# FieldBUS_RTU.net
KiCad netlist of a schematic drawn in Altium Designer
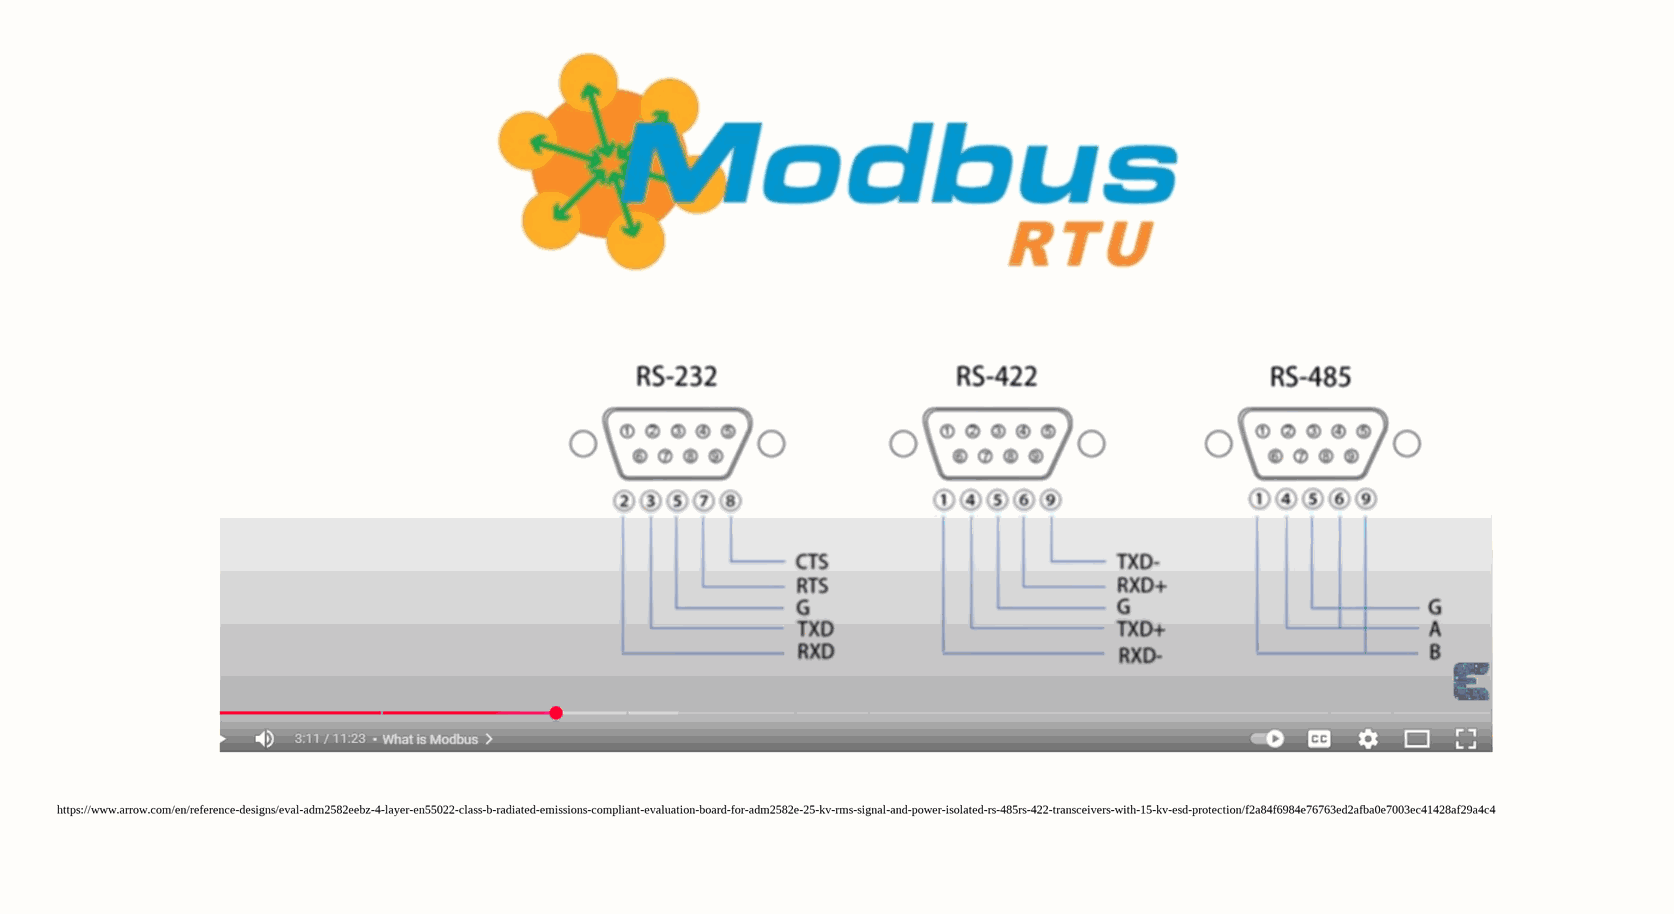
[diagram p0: FieldBUS_RTU.SchDoc, top left]
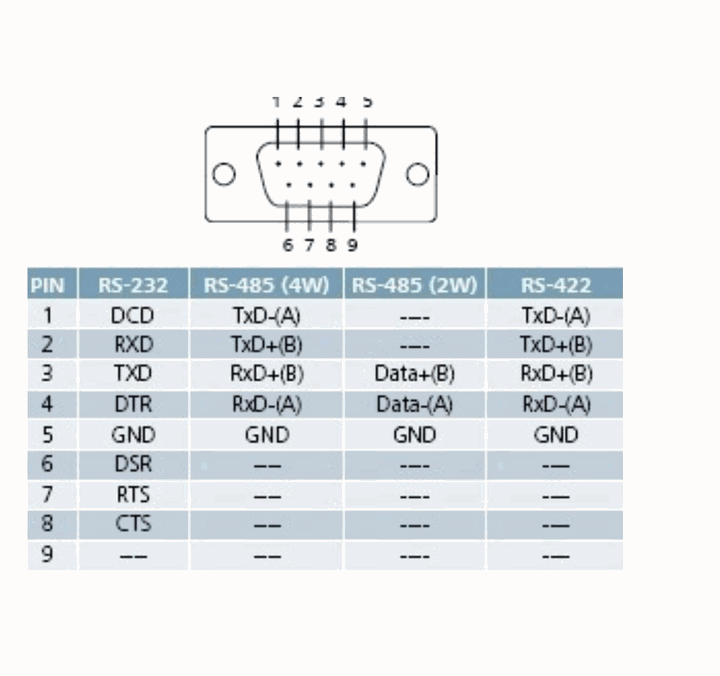
[diagram p1: FieldBUS_RTU.SchDoc, top right]
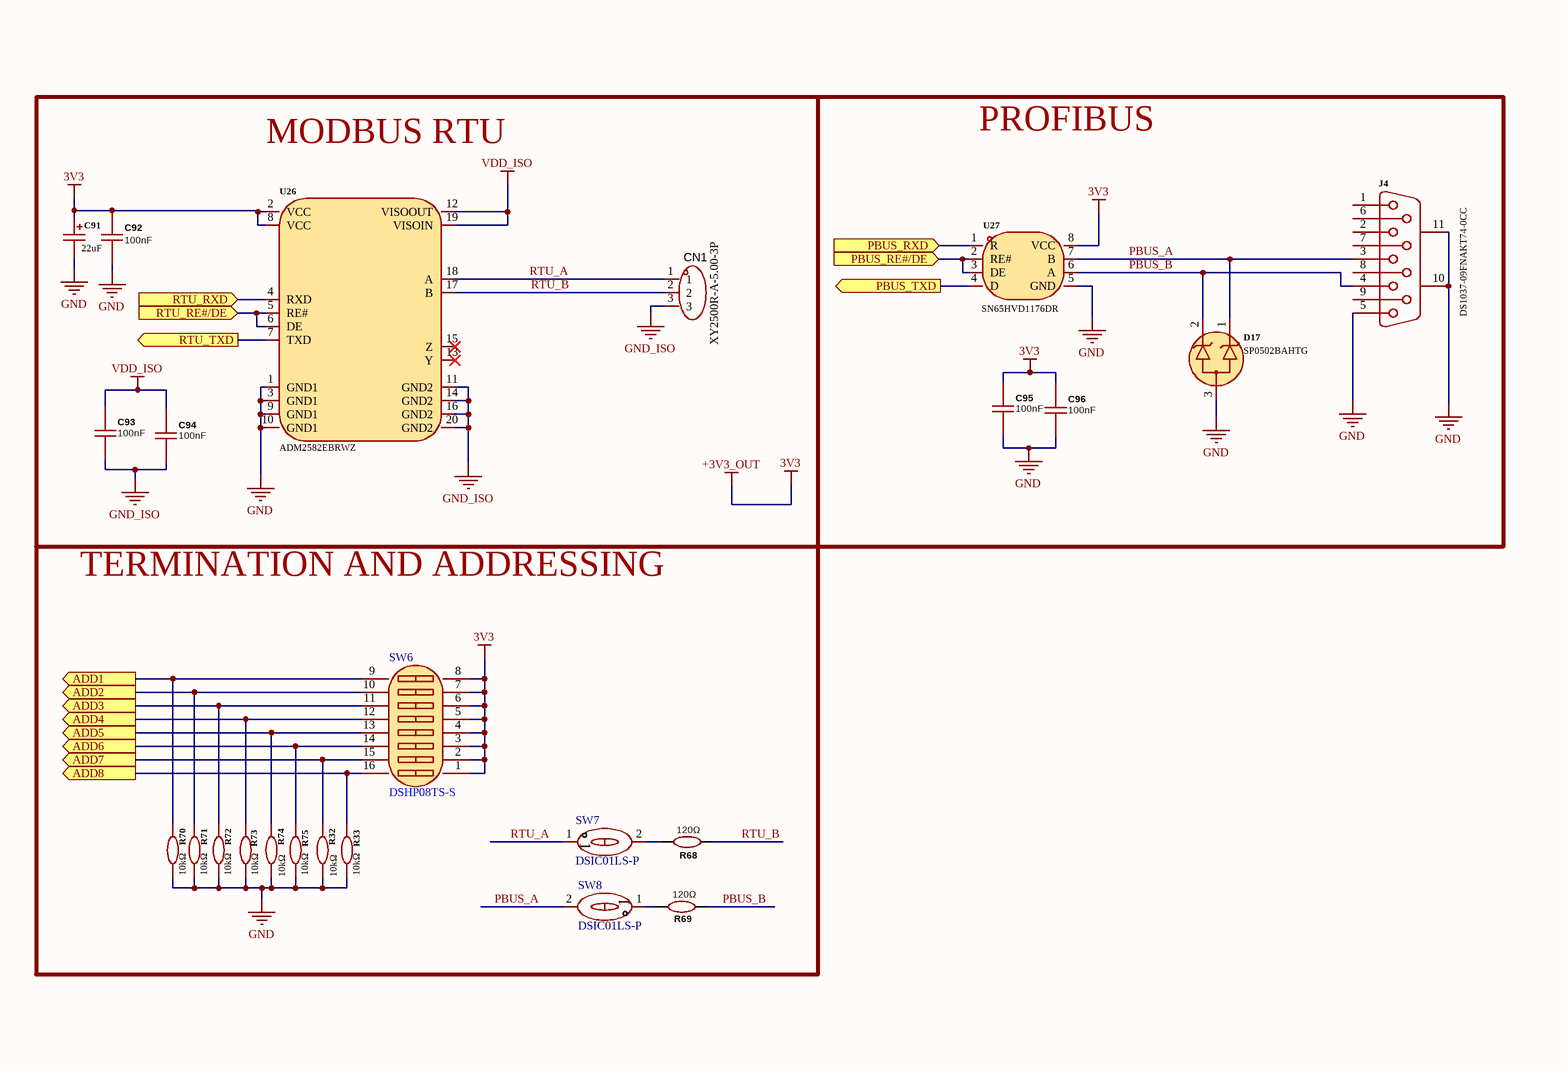
[diagram p2: FieldBUS_RTU.SchDoc, bottom left]
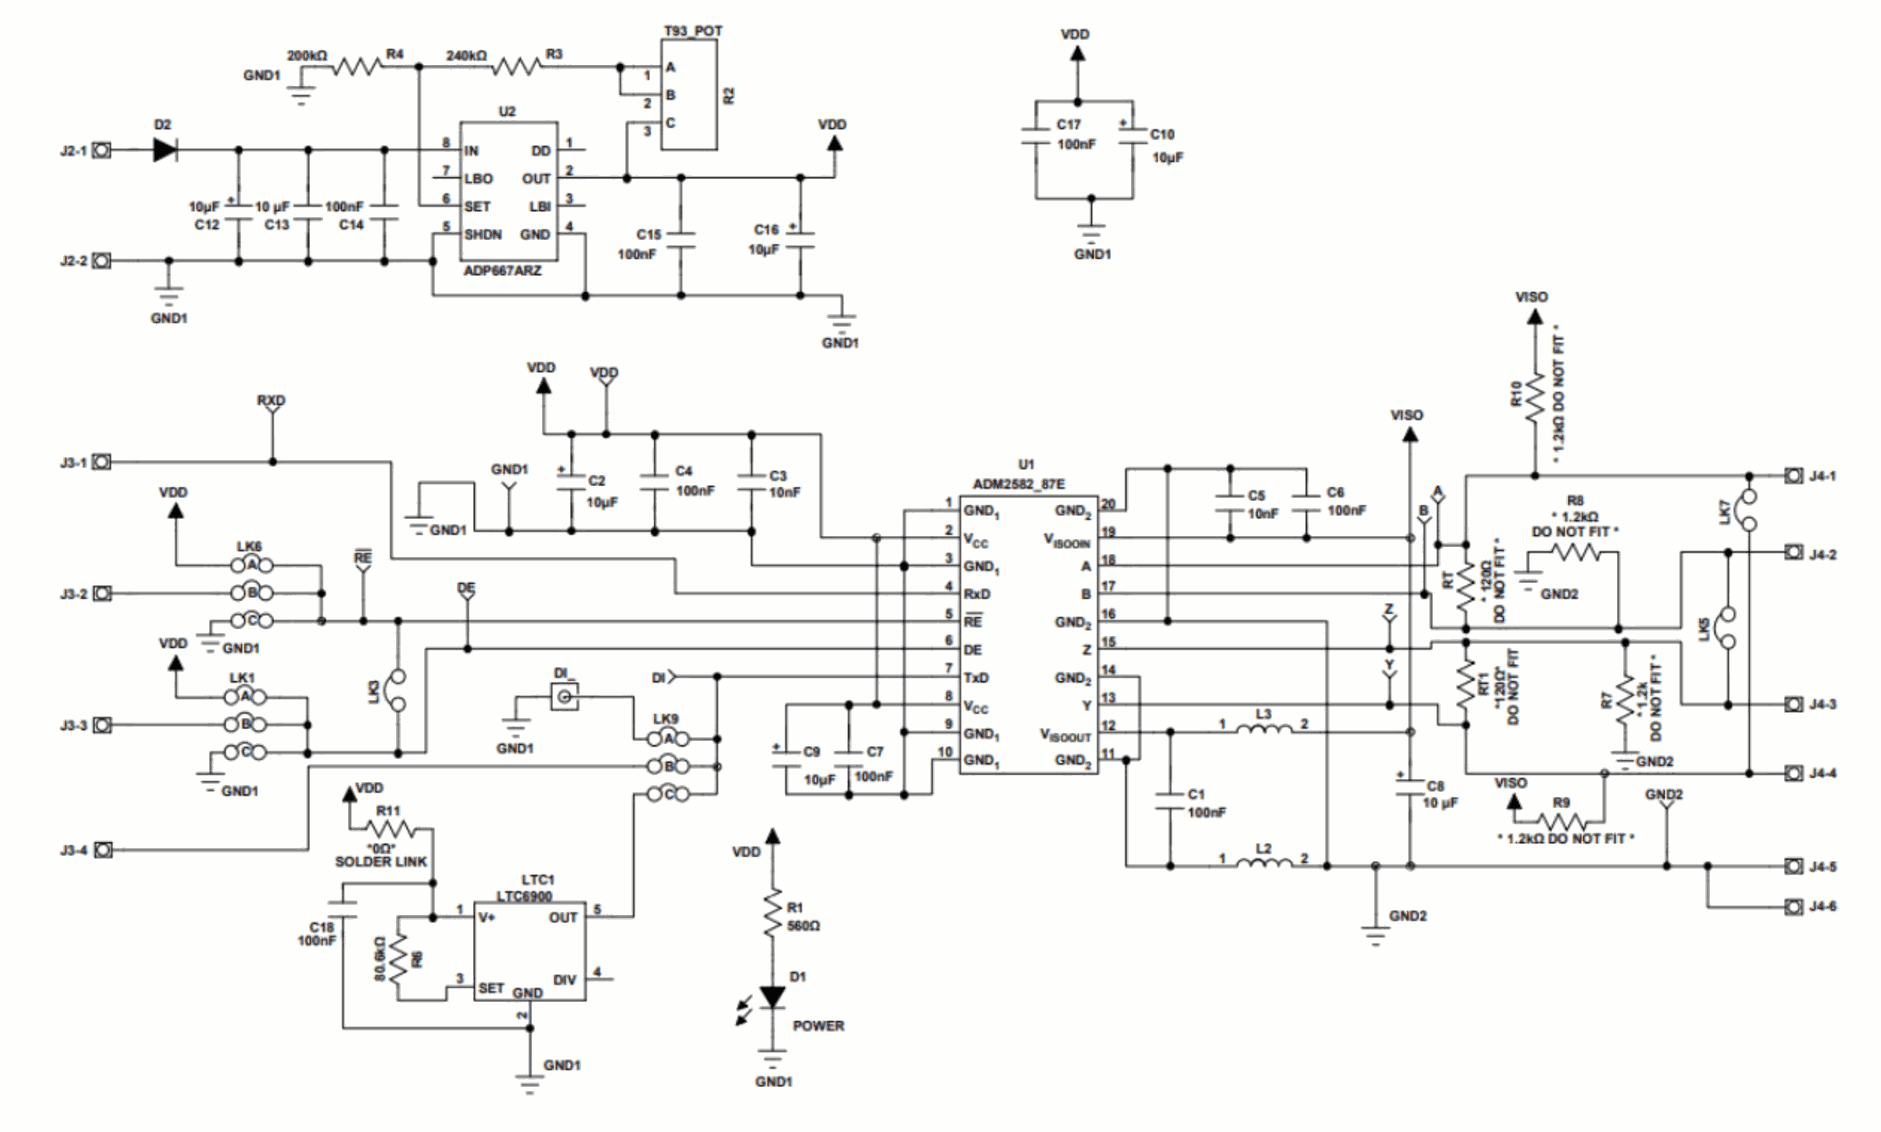
[diagram p3: FieldBUS_RTU.SchDoc, bottom right]

(export (version "E")
  (design (tool "Eeschema 10.0.6"))
  (components
    (comp (ref "C91")
      (value "22uF")
      (footprint "CASE-A_3216")
      (fields
        (field (name "MANUFACTURER") "Kyocera AVX")
        (field (name "MANUFACTURER PART") "TAJA226K010RNJ")
        (field (name "TOLERANCE") "±10%")
      )
      (libsource (lib "altium-import") (part "root_1_TAJA226K010RNJ_"))
    )
    (comp (ref "C92")
      (value "100nF")
      (footprint "C_0805")
      (fields
        (field (name "MANUFACTURER PART") "CC0805KRX7R9BB104")
        (field (name "MANUFACTURER") "YAGEO(国巨)")
      )
      (libsource (lib "altium-import") (part "root_1_100nF_"))
    )
    (comp (ref "C93")
      (value "100nF")
      (footprint "C_0805")
      (fields
        (field (name "MANUFACTURER PART") "CC0805KRX7R9BB104")
        (field (name "MANUFACTURER") "YAGEO(国巨)")
      )
      (libsource (lib "altium-import") (part "root_1_100nF_"))
    )
    (comp (ref "C94")
      (value "100nF")
      (footprint "C_0805")
      (fields
        (field (name "MANUFACTURER PART") "CC0805KRX7R9BB104")
        (field (name "MANUFACTURER") "YAGEO(国巨)")
      )
      (libsource (lib "altium-import") (part "root_1_100nF_"))
    )
    (comp (ref "C95")
      (value "100nF")
      (footprint "C_0805")
      (fields
        (field (name "MANUFACTURER PART") "CC0805KRX7R9BB104")
        (field (name "MANUFACTURER") "YAGEO(国巨)")
      )
      (libsource (lib "altium-import") (part "root_1_100nF_"))
    )
    (comp (ref "C96")
      (value "100nF")
      (footprint "C_0805")
      (fields
        (field (name "MANUFACTURER PART") "CC0805KRX7R9BB104")
        (field (name "MANUFACTURER") "YAGEO(国巨)")
      )
      (libsource (lib "altium-import") (part "root_1_100nF_"))
    )
    (comp (ref "CN1")
      (value "XY2500R-A-5.00-3P")
      (footprint "CONN-TH_XY2500R-A-5.00-3P")
      (fields (field (name "MANUFACTURER") "XINLAIYA(新莱亚)"))
      (libsource (lib "altium-import") (part "root_0_XY2500R-A-5.00-3P_"))
    )
    (comp (ref "D17")
      (value "SP0502BAHTG")
      (footprint "SOT-23-3_L2.9-W1.3-P1.90-LS2.4-BR")
      (fields (field (name "MANUFACTURER") "Littelfuse(美国力特)"))
      (libsource (lib "EsoCore_Edge_Board_V1-0.0.0") (part "SP0502BAHTG"))
    )
    (comp (ref "J4")
      (value "DS1037-09FNAKT74-0CC")
      (footprint "DSUB-TH_DS1037-09FNAKT74-0CC")
      (fields (field (name "MANUFACTURER") "CONNFLY"))
      (libsource (lib "EsoCore_Edge_Board_V1-0.0.0") (part "DS1037-09FNAKT74-0CC"))
    )
    (comp (ref "R32")
      (value "10kΩ")
      (footprint "R_0603")
      (fields
        (field (name "MANUFACTURER") "YAGEO(国巨)")
        (field (name "MANUFACTURER PART") "RC0603FR-0710KL")
        (field (name "TOLERANCE") "±1%")
      )
      (libsource (lib "altium-import") (part "root_3_RC0603FR-0710KL_"))
    )
    (comp (ref "R33")
      (value "10kΩ")
      (footprint "R_0603")
      (fields
        (field (name "MANUFACTURER") "YAGEO(国巨)")
        (field (name "MANUFACTURER PART") "RC0603FR-0710KL")
        (field (name "TOLERANCE") "±1%")
      )
      (libsource (lib "altium-import") (part "root_3_RC0603FR-0710KL_"))
    )
    (comp (ref "R68")
      (value "120Ω")
      (footprint "R_1206")
      (fields (field (name "MANUFACTURER") "YAGEO(国巨)") (field (name "MANUFACTURER PART") "RC1206FR-07120RL"))
      (libsource (lib "altium-import") (part "root_0_120Ω_"))
    )
    (comp (ref "R69")
      (value "120Ω")
      (footprint "R_1206")
      (fields (field (name "MANUFACTURER") "YAGEO(国巨)") (field (name "MANUFACTURER PART") "RC1206FR-07120RL"))
      (libsource (lib "altium-import") (part "root_0_120Ω_"))
    )
    (comp (ref "R70")
      (value "10kΩ")
      (footprint "R_0603")
      (fields
        (field (name "MANUFACTURER") "YAGEO(国巨)")
        (field (name "MANUFACTURER PART") "RC0603FR-0710KL")
        (field (name "TOLERANCE") "±1%")
      )
      (libsource (lib "altium-import") (part "root_3_RC0603FR-0710KL_"))
    )
    (comp (ref "R71")
      (value "10kΩ")
      (footprint "R_0603")
      (fields
        (field (name "MANUFACTURER") "YAGEO(国巨)")
        (field (name "MANUFACTURER PART") "RC0603FR-0710KL")
        (field (name "TOLERANCE") "±1%")
      )
      (libsource (lib "altium-import") (part "root_3_RC0603FR-0710KL_"))
    )
    (comp (ref "R72")
      (value "10kΩ")
      (footprint "R_0603")
      (fields
        (field (name "MANUFACTURER") "YAGEO(国巨)")
        (field (name "MANUFACTURER PART") "RC0603FR-0710KL")
        (field (name "TOLERANCE") "±1%")
      )
      (libsource (lib "altium-import") (part "root_3_RC0603FR-0710KL_"))
    )
    (comp (ref "R73")
      (value "10kΩ")
      (footprint "R_0603")
      (fields
        (field (name "MANUFACTURER") "YAGEO(国巨)")
        (field (name "MANUFACTURER PART") "RC0603FR-0710KL")
        (field (name "TOLERANCE") "±1%")
      )
      (libsource (lib "altium-import") (part "root_3_RC0603FR-0710KL_"))
    )
    (comp (ref "R74")
      (value "10kΩ")
      (footprint "R_0603")
      (fields
        (field (name "MANUFACTURER") "YAGEO(国巨)")
        (field (name "MANUFACTURER PART") "RC0603FR-0710KL")
        (field (name "TOLERANCE") "±1%")
      )
      (libsource (lib "altium-import") (part "root_3_RC0603FR-0710KL_"))
    )
    (comp (ref "R75")
      (value "10kΩ")
      (footprint "R_0603")
      (fields
        (field (name "MANUFACTURER") "YAGEO(国巨)")
        (field (name "MANUFACTURER PART") "RC0603FR-0710KL")
        (field (name "TOLERANCE") "±1%")
      )
      (libsource (lib "altium-import") (part "root_3_RC0603FR-0710KL_"))
    )
    (comp (ref "SW6")
      (value "DSHP08TS-S")
      (footprint "SW-SMD_DSHP08TS-S")
      (fields (field (name "MANUFACTURER") "XKB Connectivity(中国星坤)"))
      (libsource (lib "EsoCore_Edge_Board_V1-0.0.0") (part "DSHP08TS-S"))
    )
    (comp (ref "SW7")
      (value "DSIC01LS-P")
      (footprint "SW-SMD_2P-L3.5-W6.1-P2.54-LS9.8")
      (fields (field (name "MANUFACTURER") "XKB Connection(中国星坤)"))
      (libsource (lib "altium-import") (part "root_3_DSIC01LS-P_C600988_"))
    )
    (comp (ref "SW8")
      (value "DSIC01LS-P")
      (footprint "SW-SMD_2P-L3.5-W6.1-P2.54-LS9.8")
      (fields (field (name "MANUFACTURER") "XKB Connection(中国星坤)"))
      (libsource (lib "altium-import") (part "root_1_DSIC01LS-P_C600988_"))
    )
    (comp (ref "U26")
      (value "ADM2582EBRWZ")
      (footprint "SOIC-20_L13.0-W7.6-P1.27-LS10.3-BL")
      (fields (field (name "MANUFACTURER") "ADI(亚德诺)"))
      (libsource (lib "EsoCore_Edge_Board_V1-0.0.0") (part "ADM2582EBRWZ"))
    )
    (comp (ref "U27")
      (value "SN65HVD1176DR")
      (footprint "SOIC-8_L5.0-W4.0-P1.27-LS6.0-BL")
      (fields (field (name "MANUFACTURER") "TI(德州仪器)"))
      (libsource (lib "EsoCore_Edge_Board_V1-0.0.0") (part "SN65HVD1176DR"))
    )
  )
  (nets
    (net (code "1") (name "+3V3_OUT") (class "Default")
      (node (ref "C91") (pin "1") (pinfunction "1_1") (pintype "passive"))
      (node (ref "C92") (pin "2") (pinfunction "2_2") (pintype "passive"))
      (node (ref "C95") (pin "2") (pinfunction "2_2") (pintype "passive"))
      (node (ref "C96") (pin "2") (pinfunction "2_2") (pintype "passive"))
      (node (ref "SW6") (pin "1") (pinfunction "A1_1") (pintype "passive"))
      (node (ref "SW6") (pin "2") (pinfunction "A2_2") (pintype "passive"))
      (node (ref "SW6") (pin "3") (pinfunction "A3_3") (pintype "passive"))
      (node (ref "SW6") (pin "4") (pinfunction "A4_4") (pintype "passive"))
      (node (ref "SW6") (pin "5") (pinfunction "A5_5") (pintype "passive"))
      (node (ref "SW6") (pin "6") (pinfunction "A6_6") (pintype "passive"))
      (node (ref "SW6") (pin "7") (pinfunction "A7_7") (pintype "passive"))
      (node (ref "SW6") (pin "8") (pinfunction "A8_8") (pintype "passive"))
      (node (ref "U26") (pin "2") (pinfunction "VCC_2") (pintype "passive"))
      (node (ref "U26") (pin "8") (pinfunction "VCC_8") (pintype "passive"))
      (node (ref "U27") (pin "8") (pinfunction "VCC_8") (pintype "passive"))
    )
    (net (code "2") (name "/ADD1") (class "Default")
      (node (ref "R70") (pin "1") (pinfunction "1_1") (pintype "passive"))
      (node (ref "SW6") (pin "9") (pinfunction "B8_9") (pintype "passive"))
    )
    (net (code "3") (name "/ADD2") (class "Default")
      (node (ref "R71") (pin "1") (pinfunction "1_1") (pintype "passive"))
      (node (ref "SW6") (pin "10") (pinfunction "B7_10") (pintype "passive"))
    )
    (net (code "4") (name "/ADD3") (class "Default")
      (node (ref "R72") (pin "1") (pinfunction "1_1") (pintype "passive"))
      (node (ref "SW6") (pin "11") (pinfunction "B6_11") (pintype "passive"))
    )
    (net (code "5") (name "/ADD4") (class "Default")
      (node (ref "R73") (pin "1") (pinfunction "1_1") (pintype "passive"))
      (node (ref "SW6") (pin "12") (pinfunction "B5_12") (pintype "passive"))
    )
    (net (code "6") (name "/ADD5") (class "Default")
      (node (ref "R74") (pin "1") (pinfunction "1_1") (pintype "passive"))
      (node (ref "SW6") (pin "13") (pinfunction "B4_13") (pintype "passive"))
    )
    (net (code "7") (name "/ADD6") (class "Default")
      (node (ref "R75") (pin "1") (pinfunction "1_1") (pintype "passive"))
      (node (ref "SW6") (pin "14") (pinfunction "B3_14") (pintype "passive"))
    )
    (net (code "8") (name "/ADD7") (class "Default")
      (node (ref "R32") (pin "1") (pinfunction "1_1") (pintype "passive"))
      (node (ref "SW6") (pin "15") (pinfunction "B2_15") (pintype "passive"))
    )
    (net (code "9") (name "/ADD8") (class "Default")
      (node (ref "R33") (pin "1") (pinfunction "1_1") (pintype "passive"))
      (node (ref "SW6") (pin "16") (pinfunction "B1_16") (pintype "passive"))
    )
    (net (code "10") (name "/PBUS_A") (class "Default")
      (node (ref "D17") (pin "1") (pinfunction "K1_1") (pintype "passive"))
      (node (ref "J4") (pin "3") (pinfunction "3_3") (pintype "passive"))
      (node (ref "SW8") (pin "2") (pinfunction "PIN2_2") (pintype "passive"))
      (node (ref "U27") (pin "7") (pinfunction "B_7") (pintype "passive"))
    )
    (net (code "11") (name "/PBUS_B") (class "Default")
      (node (ref "D17") (pin "2") (pinfunction "K2_2") (pintype "passive"))
      (node (ref "J4") (pin "4") (pinfunction "4_4") (pintype "passive"))
      (node (ref "R69") (pin "2") (pinfunction "2_2") (pintype "passive"))
      (node (ref "U27") (pin "6") (pinfunction "A_6") (pintype "passive"))
    )
    (net (code "12") (name "/PBUS_RE#{slash}DE") (class "Default")
      (node (ref "U27") (pin "2") (pinfunction "RE#_2") (pintype "passive"))
      (node (ref "U27") (pin "3") (pinfunction "DE_3") (pintype "passive"))
    )
    (net (code "13") (name "/PBUS_RXD") (class "Default")
      (node (ref "U27") (pin "1") (pinfunction "R_1") (pintype "passive"))
    )
    (net (code "14") (name "/PBUS_TXD") (class "Default")
      (node (ref "U27") (pin "4") (pinfunction "D_4") (pintype "passive"))
    )
    (net (code "15") (name "/RTU_A") (class "Default")
      (node (ref "CN1") (pin "1") (pinfunction "1_1") (pintype "passive"))
      (node (ref "SW7") (pin "1") (pinfunction "PIN1_1") (pintype "passive"))
      (node (ref "U26") (pin "18") (pinfunction "A_18") (pintype "passive"))
    )
    (net (code "16") (name "/RTU_B") (class "Default")
      (node (ref "CN1") (pin "2") (pinfunction "2_2") (pintype "passive"))
      (node (ref "R68") (pin "2") (pinfunction "2_2") (pintype "passive"))
      (node (ref "U26") (pin "17") (pinfunction "B_17") (pintype "passive"))
    )
    (net (code "17") (name "/RTU_RE#{slash}DE") (class "Default")
      (node (ref "U26") (pin "5") (pinfunction "RE#_5") (pintype "passive"))
      (node (ref "U26") (pin "6") (pinfunction "DE_6") (pintype "passive"))
    )
    (net (code "18") (name "/RTU_RXD") (class "Default")
      (node (ref "U26") (pin "4") (pinfunction "RXD_4") (pintype "passive"))
    )
    (net (code "19") (name "/RTU_TXD") (class "Default")
      (node (ref "U26") (pin "7") (pinfunction "TXD_7") (pintype "passive"))
    )
    (net (code "20") (name "GND") (class "Default")
      (node (ref "C91") (pin "2") (pinfunction "2_2") (pintype "passive"))
      (node (ref "C92") (pin "1") (pinfunction "1_1") (pintype "passive"))
      (node (ref "C95") (pin "1") (pinfunction "1_1") (pintype "passive"))
      (node (ref "C96") (pin "1") (pinfunction "1_1") (pintype "passive"))
      (node (ref "D17") (pin "3") (pinfunction "A_3") (pintype "passive"))
      (node (ref "J4") (pin "10") (pinfunction "MH1_10") (pintype "passive"))
      (node (ref "J4") (pin "11") (pinfunction "MH2_11") (pintype "passive"))
      (node (ref "J4") (pin "5") (pinfunction "5_5") (pintype "passive"))
      (node (ref "R32") (pin "2") (pinfunction "2_2") (pintype "passive"))
      (node (ref "R33") (pin "2") (pinfunction "2_2") (pintype "passive"))
      (node (ref "R70") (pin "2") (pinfunction "2_2") (pintype "passive"))
      (node (ref "R71") (pin "2") (pinfunction "2_2") (pintype "passive"))
      (node (ref "R72") (pin "2") (pinfunction "2_2") (pintype "passive"))
      (node (ref "R73") (pin "2") (pinfunction "2_2") (pintype "passive"))
      (node (ref "R74") (pin "2") (pinfunction "2_2") (pintype "passive"))
      (node (ref "R75") (pin "2") (pinfunction "2_2") (pintype "passive"))
      (node (ref "U26") (pin "1") (pinfunction "GND1_1") (pintype "passive"))
      (node (ref "U26") (pin "10") (pinfunction "GND1_10") (pintype "passive"))
      (node (ref "U26") (pin "3") (pinfunction "GND1_3") (pintype "passive"))
      (node (ref "U26") (pin "9") (pinfunction "GND1_9") (pintype "passive"))
      (node (ref "U27") (pin "5") (pinfunction "GND_5") (pintype "passive"))
    )
    (net (code "21") (name "GND_ISO") (class "Default")
      (node (ref "C93") (pin "1") (pinfunction "1_1") (pintype "passive"))
      (node (ref "C94") (pin "1") (pinfunction "1_1") (pintype "passive"))
      (node (ref "CN1") (pin "3") (pinfunction "3_3") (pintype "passive"))
      (node (ref "U26") (pin "11") (pinfunction "GND2_11") (pintype "passive"))
      (node (ref "U26") (pin "14") (pinfunction "GND2_14") (pintype "passive"))
      (node (ref "U26") (pin "16") (pinfunction "GND2_16") (pintype "passive"))
      (node (ref "U26") (pin "20") (pinfunction "GND2_20") (pintype "passive"))
    )
    (net (code "22") (name "Net-(SW7-PIN2)") (class "Default")
      (node (ref "R68") (pin "1") (pinfunction "1_1") (pintype "passive"))
      (node (ref "SW7") (pin "2") (pinfunction "PIN2_2") (pintype "passive"))
    )
    (net (code "23") (name "Net-(SW8-PIN1)") (class "Default")
      (node (ref "R69") (pin "1") (pinfunction "1_1") (pintype "passive"))
      (node (ref "SW8") (pin "1") (pinfunction "PIN1_1") (pintype "passive"))
    )
    (net (code "24") (name "VDD_ISO") (class "Default")
      (node (ref "C93") (pin "2") (pinfunction "2_2") (pintype "passive"))
      (node (ref "C94") (pin "2") (pinfunction "2_2") (pintype "passive"))
      (node (ref "U26") (pin "12") (pinfunction "VISOOUT_12") (pintype "passive"))
      (node (ref "U26") (pin "19") (pinfunction "VISOIN_19") (pintype "passive"))
    )
    (net (code "25") (name "unconnected-(J4-Pad1)") (class "Default")
      (node (ref "J4") (pin "1") (pinfunction "1_1") (pintype "passive"))
    )
    (net (code "26") (name "unconnected-(J4-Pad2)") (class "Default")
      (node (ref "J4") (pin "2") (pinfunction "2_2") (pintype "passive"))
    )
    (net (code "27") (name "unconnected-(J4-Pad6)") (class "Default")
      (node (ref "J4") (pin "6") (pinfunction "6_6") (pintype "passive"))
    )
    (net (code "28") (name "unconnected-(J4-Pad7)") (class "Default")
      (node (ref "J4") (pin "7") (pinfunction "7_7") (pintype "passive"))
    )
    (net (code "29") (name "unconnected-(J4-Pad8)") (class "Default")
      (node (ref "J4") (pin "8") (pinfunction "8_8") (pintype "passive"))
    )
    (net (code "30") (name "unconnected-(J4-Pad9)") (class "Default")
      (node (ref "J4") (pin "9") (pinfunction "9_9") (pintype "passive"))
    )
    (net (code "31") (name "unconnected-(U26-Y-Pad13)") (class "Default")
      (node (ref "U26") (pin "13") (pinfunction "Y_13") (pintype "passive+no_connect"))
    )
    (net (code "32") (name "unconnected-(U26-Z-Pad15)") (class "Default")
      (node (ref "U26") (pin "15") (pinfunction "Z_15") (pintype "passive+no_connect"))
    )
  )
)
